# Connectors.net
KiCad netlist of a schematic drawn in Altium Designer
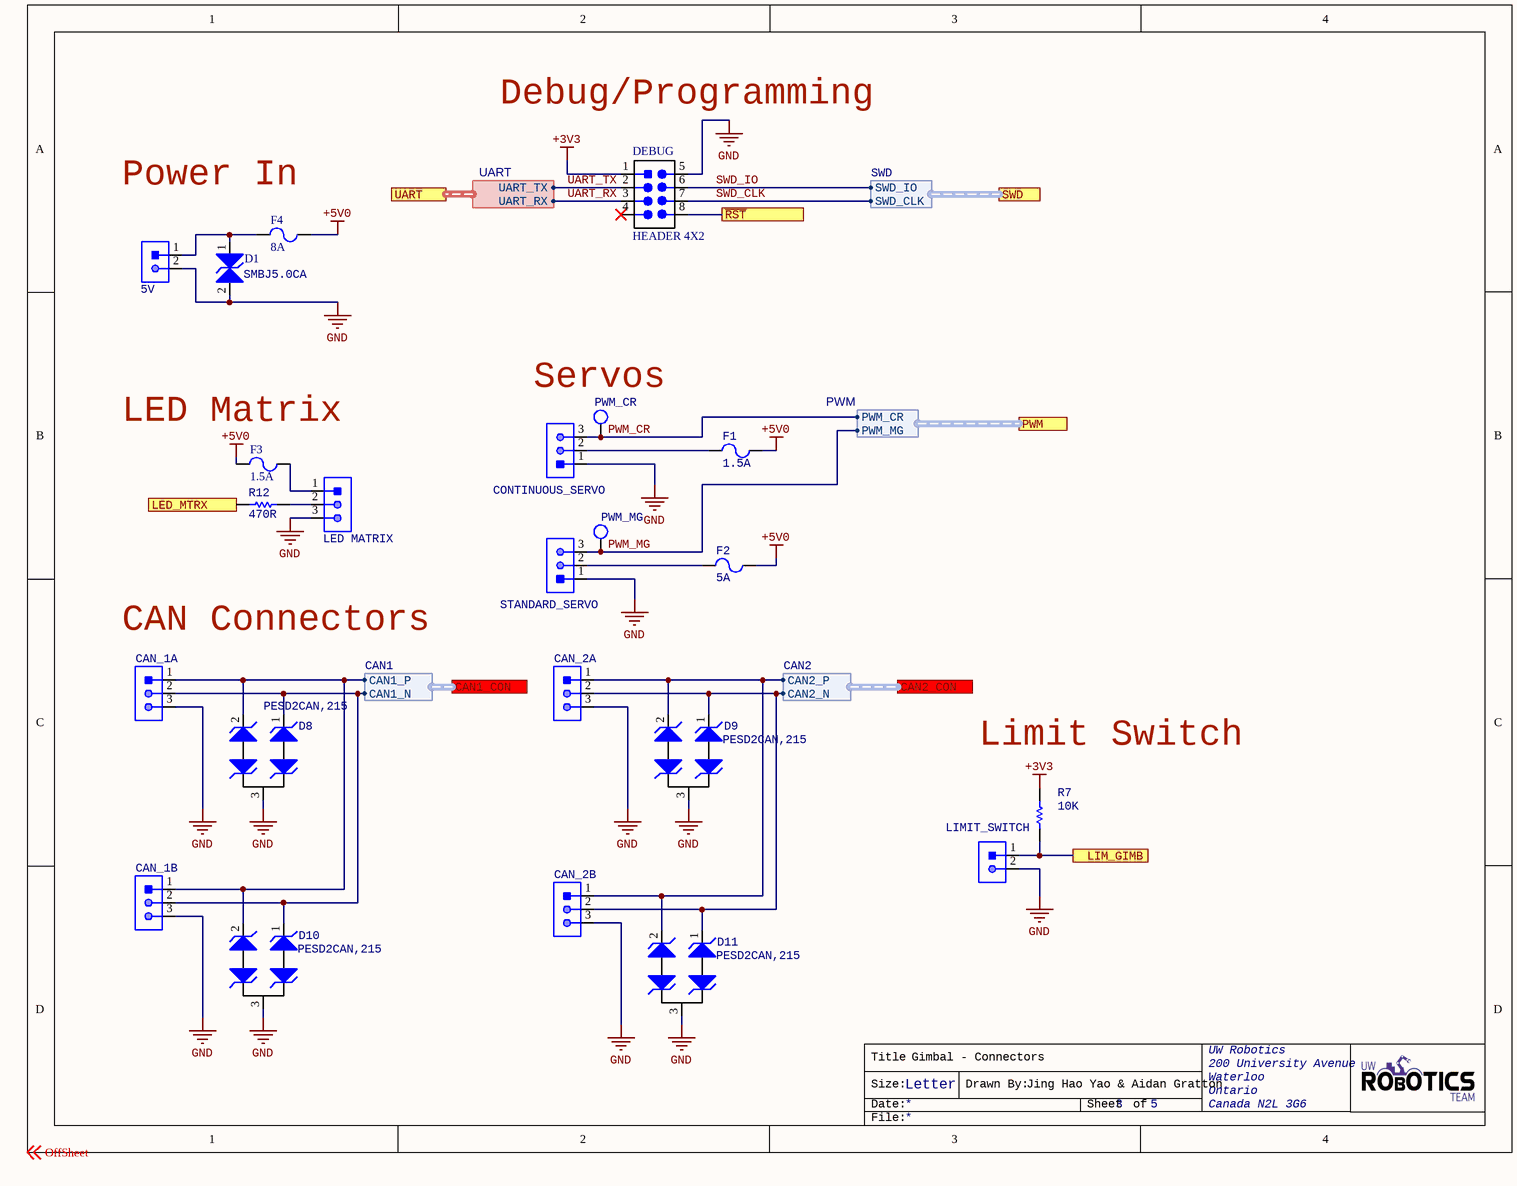
[diagram p0: Connectors.SchDoc]

(export (version "E")
  (design (tool "Eeschema 10.0.6"))
  (components
    (comp (ref "5V")
      (value "CON_2M_SM4")
      (footprint "JST-B2B-SM4-TB")
      (fields
        (field (name "MANUFACTURER") "JST")
        (field (name "MANUFACTURER PART NUMBER") "B2B-PH-SM4-TB(LF)(SN)")
      )
      (libsource (lib "UWRT_Schematic_Library_2020") (part "CON_2M_SM4"))
    )
    (comp (ref "CAN_1A")
      (value "CON_3M_SM4")
      (footprint "JST-B3B-SM4-TB")
      (fields
        (field (name "MANUFACTURER") "JST")
        (field (name "MANUFACTURER PART NUMBER") "B3B-PH-SM4-TB(LF)(SN)")
      )
      (libsource (lib "") (part "CON_3M_SM4_1"))
    )
    (comp (ref "CAN_1B")
      (value "CON_3M_SM4")
      (footprint "JST-B3B-SM4-TB")
      (fields
        (field (name "MANUFACTURER") "JST")
        (field (name "MANUFACTURER PART NUMBER") "B3B-PH-SM4-TB(LF)(SN)")
      )
      (libsource (lib "") (part "CON_3M_SM4_1"))
    )
    (comp (ref "CAN_2A")
      (value "CON_3M_SM4")
      (footprint "JST-B3B-SM4-TB")
      (fields
        (field (name "MANUFACTURER") "JST")
        (field (name "MANUFACTURER PART NUMBER") "B3B-PH-SM4-TB(LF)(SN)")
      )
      (libsource (lib "") (part "CON_3M_SM4_1"))
    )
    (comp (ref "CAN_2B")
      (value "CON_3M_SM4")
      (footprint "JST-B3B-SM4-TB")
      (fields
        (field (name "MANUFACTURER") "JST")
        (field (name "MANUFACTURER PART NUMBER") "B3B-PH-SM4-TB(LF)(SN)")
      )
      (libsource (lib "") (part "CON_3M_SM4_1"))
    )
    (comp (ref "CONTINUOUS_SERVO")
      (value "CON_3M_SM4")
      (footprint "JST-B3B-SM4-TB")
      (fields
        (field (name "MANUFACTURER") "JST")
        (field (name "MANUFACTURER PART NUMBER") "B3B-PH-SM4-TB(LF)(SN)")
      )
      (libsource (lib "UWRT_Schematic_Library_2020") (part "CON_3M_SM4"))
    )
    (comp (ref "D1")
      (value "TVS_DIODE_BIDIRECTIONAL")
      (footprint "TVS_DIODE_BIDIRECTIONAL")
      (description "TVS DIODE 5V 9.2V DO214AA")
      (fields
        (field (name "MANUFACTURER") "Nexperia USA Inc.")
        (field (name "MANUFACTURER PART NUMBER 1") "SMBJ5.0CA")
      )
      (libsource (lib "UWRT_Schematic_Library_2020") (part "TVS_DIODE_BIDIRECTIONAL"))
    )
    (comp (ref "D8")
      (value "TVS_DIODE_CAN")
      (footprint "TVS_DIODE_CAN")
      (description "TVS DIODE 24V 41V SOT323-3")
      (fields
        (field (name "MANUFACTURER") "Nexperia USA Inc.")
        (field (name "MANUFACTURER PART NUMBER") "PESD2CAN,215")
      )
      (libsource (lib "UWRT_Schematic_Library_2020") (part "TVS_DIODE_CAN"))
    )
    (comp (ref "D9")
      (value "TVS_DIODE_CAN")
      (footprint "TVS_DIODE_CAN")
      (description "TVS DIODE 24V 41V SOT323-3")
      (fields
        (field (name "MANUFACTURER") "Nexperia USA Inc.")
        (field (name "MANUFACTURER PART NUMBER") "PESD2CAN,215")
      )
      (libsource (lib "UWRT_Schematic_Library_2020") (part "TVS_DIODE_CAN"))
    )
    (comp (ref "D10")
      (value "TVS_DIODE_CAN")
      (footprint "TVS_DIODE_CAN")
      (description "TVS DIODE 24V 41V SOT323-3")
      (fields
        (field (name "MANUFACTURER") "Nexperia USA Inc.")
        (field (name "MANUFACTURER PART NUMBER") "PESD2CAN,215")
      )
      (libsource (lib "UWRT_Schematic_Library_2020") (part "TVS_DIODE_CAN"))
    )
    (comp (ref "D11")
      (value "TVS_DIODE_CAN")
      (footprint "TVS_DIODE_CAN")
      (description "TVS DIODE 24V 41V SOT323-3")
      (fields
        (field (name "MANUFACTURER") "Nexperia USA Inc.")
        (field (name "MANUFACTURER PART NUMBER") "PESD2CAN,215")
      )
      (libsource (lib "UWRT_Schematic_Library_2020") (part "TVS_DIODE_CAN"))
    )
    (comp (ref "DEBUG")
      (value "HEADER 4X2")
      (footprint "HEADER_2X4")
      (description "CONN HEADER VERT 8POS 2.54MM")
      (libsource (lib "UWRT_Schematic_Library_2020") (part "HEADER 4X2"))
    )
    (comp (ref "F1")
      (value "FUSE_1.5A_0603")
      (footprint "FUSE_0603")
      (description "FUSE SMD 1.5A 32V")
      (fields (field (name "CURRENT RATING") "1.5A"))
      (libsource (lib "UWRT_Schematic_Library_2020") (part "FUSE_1.5A_0603"))
    )
    (comp (ref "F2")
      (value "FUSE_5A_0603")
      (footprint "FUSE_0603")
      (description "FUSE SMD 5A 32V")
      (fields (field (name "CURRENT RATING") "5A"))
      (libsource (lib "UWRT_Schematic_Library_2020") (part "FUSE_5A_0603"))
    )
    (comp (ref "F3")
      (value "FUSE_1.5A_0603")
      (footprint "FUSE_0603")
      (description "FUSE SMD 1.5A 32V")
      (fields (field (name "CURRENT RATING") "1.5A"))
      (libsource (lib "UWRT_Schematic_Library_2020") (part "FUSE_1.5A_0603"))
    )
    (comp (ref "F4")
      (value "FUSE_8A_0603")
      (footprint "FUSE_0603")
      (description "FUSE SMD 8A 63V")
      (fields (field (name "CURRENT RATING") "8A"))
      (libsource (lib "UWRT_Schematic_Library_2020") (part "FUSE_8A_0603"))
    )
    (comp (ref "LED MATRIX")
      (value "CON_3M_SM4")
      (footprint "JST-B3B-SM4-TB")
      (fields
        (field (name "MANUFACTURER") "JST")
        (field (name "MANUFACTURER PART NUMBER") "B3B-PH-SM4-TB(LF)(SN)")
      )
      (libsource (lib "") (part "CON_3M_SM4_2"))
    )
    (comp (ref "LIMIT_SWITCH")
      (value "CON_2M_SM4")
      (footprint "JST-B2B-SM4-TB")
      (fields
        (field (name "MANUFACTURER") "JST")
        (field (name "MANUFACTURER PART NUMBER") "B2B-PH-SM4-TB(LF)(SN)")
      )
      (libsource (lib "UWRT_Schematic_Library_2020") (part "CON_2M_SM4"))
    )
    (comp (ref "PWM_CR")
      (value "TESTPOINT_LOOP")
      (footprint "TESTPOINT_LOOP")
      (description "Loop testpoint through-hole pad")
      (fields (field (name "MANUFACTURER") "Keystone Electronics"))
      (libsource (lib "UWRT_Schematic_Library_2020") (part "TESTPOINT_LOOP"))
    )
    (comp (ref "PWM_MG")
      (value "TESTPOINT_LOOP")
      (footprint "TESTPOINT_LOOP")
      (description "Loop testpoint through-hole pad")
      (fields (field (name "MANUFACTURER") "Keystone Electronics"))
      (libsource (lib "UWRT_Schematic_Library_2020") (part "TESTPOINT_LOOP"))
    )
    (comp (ref "R7")
      (value "10K")
      (footprint "RESC0603(1608)_N")
      (description "RES SMD 10K OHM 5% 1/10W 0603")
      (fields (field (name "MANUFACTURER") "Yageo") (field (name "TOLERANCE") "5%"))
      (libsource (lib "UWRT_Schematic_Library_2020") (part "RES_10K_0603"))
    )
    (comp (ref "R12")
      (value "470R")
      (footprint "RESC0603(1608)_N")
      (description "RES SMD 470 OHM 1% 1/10W 0603")
      (fields (field (name "MANUFACTURER") "Yageo") (field (name "MPN") "AC0603FR-07470RL"))
      (libsource (lib "UWRT_Schematic_Library_2020") (part "RES_470R_0603"))
    )
    (comp (ref "STANDARD_SERVO")
      (value "CON_3M_SM4")
      (footprint "JST-B3B-SM4-TB")
      (fields
        (field (name "MANUFACTURER") "JST")
        (field (name "MANUFACTURER PART NUMBER") "B3B-PH-SM4-TB(LF)(SN)")
      )
      (libsource (lib "UWRT_Schematic_Library_2020") (part "CON_3M_SM4"))
    )
  )
  (nets
    (net (code "6") (name "+3V3") (class "Default")
      (node (ref "DEBUG") (pin "1") (pinfunction "VCC_1") (pintype "passive"))
      (node (ref "R7") (pin "2") (pinfunction "2_2") (pintype "passive"))
    )
    (net (code "7") (name "+5V0") (class "Default")
      (node (ref "F1") (pin "2") (pinfunction "2_2") (pintype "passive"))
      (node (ref "F2") (pin "2") (pinfunction "2_2") (pintype "passive"))
      (node (ref "F3") (pin "1") (pinfunction "1_1") (pintype "passive"))
      (node (ref "F4") (pin "2") (pinfunction "2_2") (pintype "passive"))
    )
    (net (code "8") (name "/LED_MTRX") (class "Default")
      (node (ref "R12") (pin "1") (pinfunction "1_1") (pintype "passive"))
    )
    (net (code "9") (name "/LIM_GIMB") (class "Default")
      (node (ref "LIMIT_SWITCH") (pin "1") (pinfunction "1_1") (pintype "passive"))
      (node (ref "R7") (pin "1") (pinfunction "1_1") (pintype "passive"))
    )
    (net (code "10") (name "/PWM_CR") (class "Default")
      (node (ref "CONTINUOUS_SERVO") (pin "3") (pinfunction "3_3") (pintype "passive"))
      (node (ref "PWM_CR") (pin "1") (pintype "passive"))
    )
    (net (code "11") (name "/PWM_MG") (class "Default")
      (node (ref "PWM_MG") (pin "1") (pintype "passive"))
      (node (ref "STANDARD_SERVO") (pin "3") (pinfunction "3_3") (pintype "passive"))
    )
    (net (code "12") (name "/SWD_CLK") (class "Default")
      (node (ref "DEBUG") (pin "7") (pinfunction "3_7") (pintype "passive"))
    )
    (net (code "13") (name "/SWD_IO") (class "Default")
      (node (ref "DEBUG") (pin "6") (pinfunction "2_6") (pintype "passive"))
    )
    (net (code "14") (name "/UART_RX") (class "Default")
      (node (ref "DEBUG") (pin "3") (pinfunction "3_3") (pintype "passive"))
    )
    (net (code "15") (name "/UART_TX") (class "Default")
      (node (ref "DEBUG") (pin "2") (pinfunction "2_2") (pintype "passive"))
    )
    (net (code "21") (name "/~{RST}") (class "Default")
      (node (ref "DEBUG") (pin "8") (pinfunction "4_8") (pintype "passive"))
    )
    (net (code "22") (name "GND") (class "Default")
      (node (ref "5V") (pin "2") (pinfunction "2_2") (pintype "passive"))
      (node (ref "CAN_1A") (pin "3") (pinfunction "3_3") (pintype "passive"))
      (node (ref "CAN_1B") (pin "3") (pinfunction "3_3") (pintype "passive"))
      (node (ref "CAN_2A") (pin "3") (pinfunction "3_3") (pintype "passive"))
      (node (ref "CAN_2B") (pin "3") (pinfunction "3_3") (pintype "passive"))
      (node (ref "CONTINUOUS_SERVO") (pin "1") (pinfunction "1_1") (pintype "passive"))
      (node (ref "D1") (pin "2") (pinfunction "2_2") (pintype "passive"))
      (node (ref "D10") (pin "3") (pinfunction "3_3") (pintype "passive"))
      (node (ref "D11") (pin "3") (pinfunction "3_3") (pintype "passive"))
      (node (ref "D8") (pin "3") (pinfunction "3_3") (pintype "passive"))
      (node (ref "D9") (pin "3") (pinfunction "3_3") (pintype "passive"))
      (node (ref "DEBUG") (pin "5") (pinfunction "GND_5") (pintype "passive"))
      (node (ref "LED MATRIX") (pin "3") (pinfunction "3_3") (pintype "passive"))
      (node (ref "LIMIT_SWITCH") (pin "2") (pinfunction "2_2") (pintype "passive"))
      (node (ref "STANDARD_SERVO") (pin "1") (pinfunction "1_1") (pintype "passive"))
    )
    (net (code "23") (name "Net-(5V-Pad1)") (class "Default")
      (node (ref "5V") (pin "1") (pinfunction "1_1") (pintype "passive"))
      (node (ref "D1") (pin "1") (pinfunction "1_1") (pintype "passive"))
      (node (ref "F4") (pin "1") (pinfunction "1_1") (pintype "passive"))
    )
    (net (code "24") (name "Net-(CAN_1A-Pad1)") (class "Default")
      (node (ref "CAN_1A") (pin "1") (pinfunction "1_1") (pintype "passive"))
      (node (ref "CAN_1B") (pin "1") (pinfunction "1_1") (pintype "passive"))
      (node (ref "D10") (pin "2") (pinfunction "2_2") (pintype "passive"))
      (node (ref "D8") (pin "2") (pinfunction "2_2") (pintype "passive"))
    )
    (net (code "25") (name "Net-(CAN_1A-Pad2)") (class "Default")
      (node (ref "CAN_1A") (pin "2") (pinfunction "2_2") (pintype "passive"))
      (node (ref "CAN_1B") (pin "2") (pinfunction "2_2") (pintype "passive"))
      (node (ref "D10") (pin "1") (pinfunction "1_1") (pintype "passive"))
      (node (ref "D8") (pin "1") (pinfunction "1_1") (pintype "passive"))
    )
    (net (code "26") (name "Net-(CAN_2A-Pad1)") (class "Default")
      (node (ref "CAN_2A") (pin "1") (pinfunction "1_1") (pintype "passive"))
      (node (ref "CAN_2B") (pin "1") (pinfunction "1_1") (pintype "passive"))
      (node (ref "D11") (pin "2") (pinfunction "2_2") (pintype "passive"))
      (node (ref "D9") (pin "2") (pinfunction "2_2") (pintype "passive"))
    )
    (net (code "27") (name "Net-(CAN_2A-Pad2)") (class "Default")
      (node (ref "CAN_2A") (pin "2") (pinfunction "2_2") (pintype "passive"))
      (node (ref "CAN_2B") (pin "2") (pinfunction "2_2") (pintype "passive"))
      (node (ref "D11") (pin "1") (pinfunction "1_1") (pintype "passive"))
      (node (ref "D9") (pin "1") (pinfunction "1_1") (pintype "passive"))
    )
    (net (code "28") (name "Net-(CONTINUOUS_SERVO-Pad2)") (class "Default")
      (node (ref "CONTINUOUS_SERVO") (pin "2") (pinfunction "2_2") (pintype "passive"))
      (node (ref "F1") (pin "1") (pinfunction "1_1") (pintype "passive"))
    )
    (net (code "29") (name "Net-(F2-Pad1)") (class "Default")
      (node (ref "F2") (pin "1") (pinfunction "1_1") (pintype "passive"))
      (node (ref "STANDARD_SERVO") (pin "2") (pinfunction "2_2") (pintype "passive"))
    )
    (net (code "30") (name "Net-(F3-Pad2)") (class "Default")
      (node (ref "F3") (pin "2") (pinfunction "2_2") (pintype "passive"))
      (node (ref "LED MATRIX") (pin "1") (pinfunction "1_1") (pintype "passive"))
    )
    (net (code "31") (name "Net-(LED MATRIX-Pad2)") (class "Default")
      (node (ref "LED MATRIX") (pin "2") (pinfunction "2_2") (pintype "passive"))
      (node (ref "R12") (pin "2") (pinfunction "2_2") (pintype "passive"))
    )
    (net (code "33") (name "unconnected-(DEBUG-Pad4)") (class "Default")
      (node (ref "DEBUG") (pin "4") (pinfunction "4_4") (pintype "passive+no_connect"))
    )
  )
)
